# VF_OrdRes_PCB.net
KiCad netlist of a schematic drawn in EAGLE
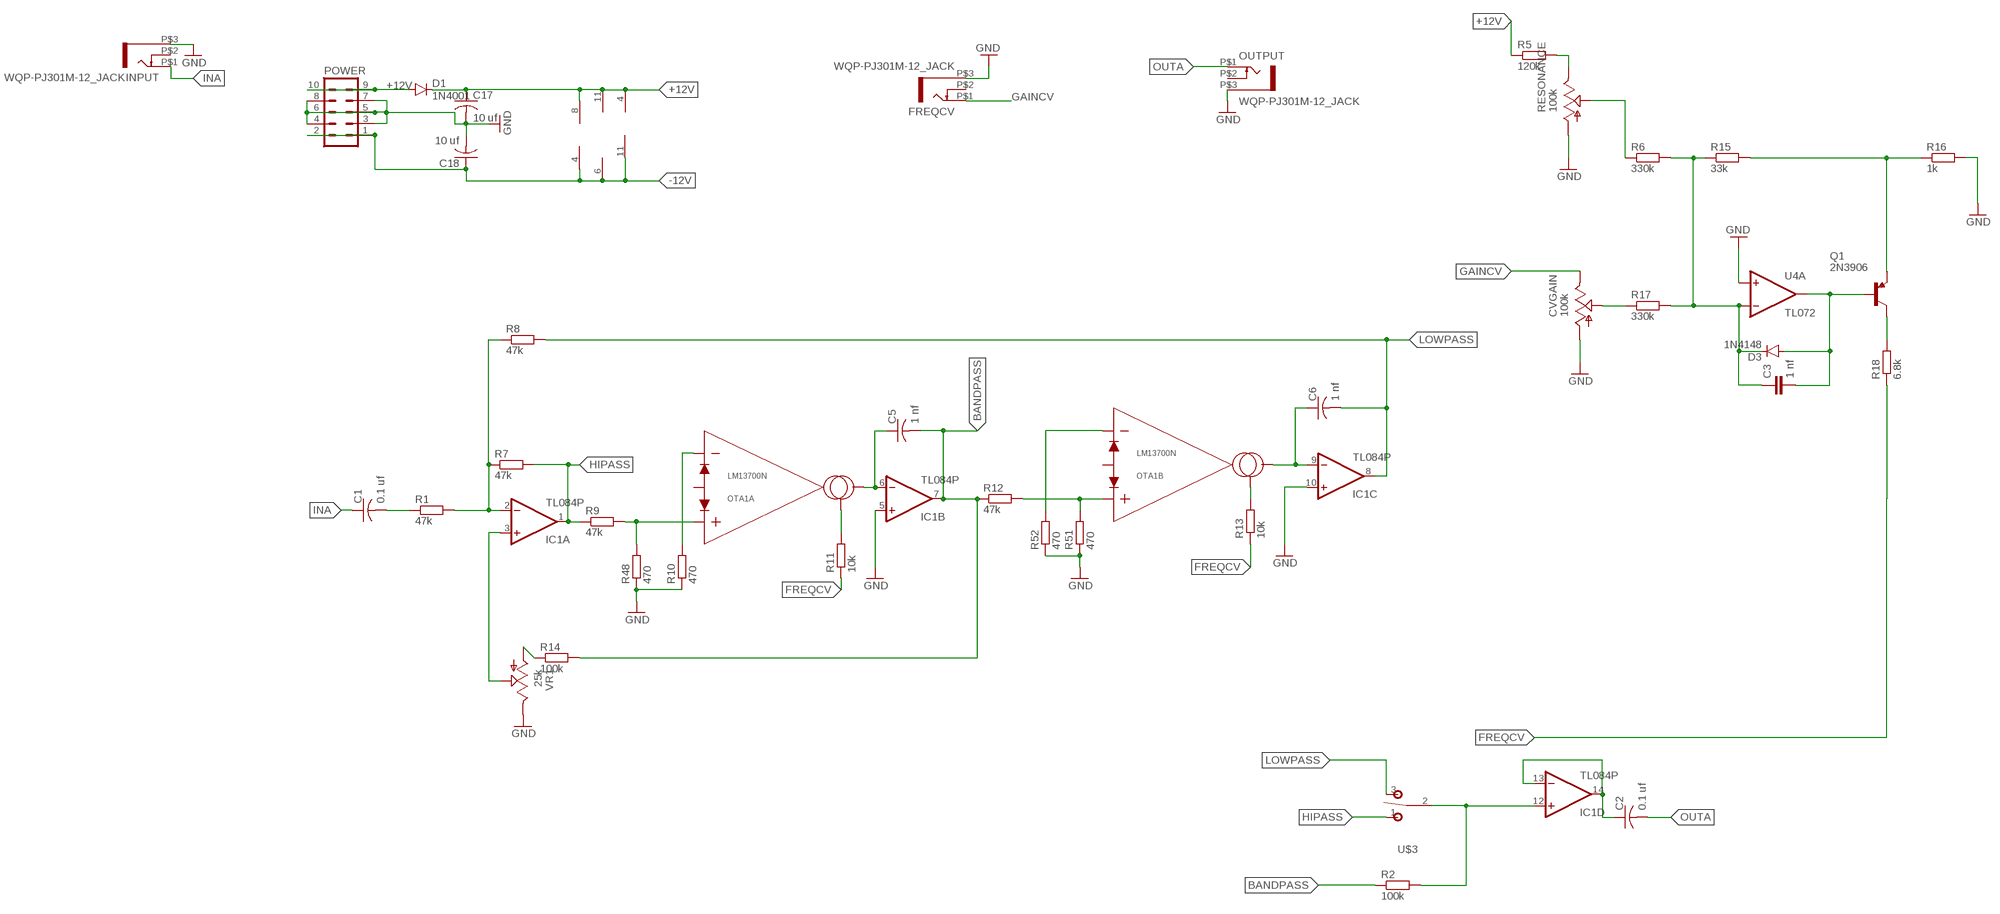
[diagram p0: schematic, sheet 1]

(export (version "E")
  (design (tool "Eeschema 10.0.6"))
  (components
    (comp (ref "C1")
      (value "0.1 uf")
      (footprint "eagle-import:C050-030X075")
      (libsource (lib "eagle-import") (part "C-US050-030X075"))
    )
    (comp (ref "C2")
      (value "0.1 uf")
      (footprint "eagle-import:C050-030X075")
      (libsource (lib "eagle-import") (part "C-US050-030X075"))
    )
    (comp (ref "C3")
      (value "1 nf")
      (footprint "eagle-import:C050-025X075")
      (libsource (lib "eagle-import") (part "C-EU050-025X075"))
    )
    (comp (ref "C5")
      (value "1 nf")
      (footprint "eagle-import:C050-030X075")
      (libsource (lib "eagle-import") (part "C-US050-030X075"))
    )
    (comp (ref "C6")
      (value "1 nf")
      (footprint "eagle-import:C050-030X075")
      (libsource (lib "eagle-import") (part "C-US050-030X075"))
    )
    (comp (ref "C17")
      (value "10 uf")
      (footprint "eagle-import:C050-030X075")
      (libsource (lib "eagle-import") (part "C-US050-030X075"))
    )
    (comp (ref "C18")
      (value "10 uf")
      (footprint "eagle-import:C050-030X075")
      (libsource (lib "eagle-import") (part "C-US050-030X075"))
    )
    (comp (ref "CVGAIN")
      (value "100k")
      (footprint "eagle-import:9MM_SNAP-IN_POT")
      (libsource (lib "eagle-import") (part "9MM_SNAP-IN_POT_"))
    )
    (comp (ref "D1")
      (value "1N4001")
      (footprint "eagle-import:DO41-10")
      (libsource (lib "eagle-import") (part "1N4004"))
    )
    (comp (ref "D3")
      (value "1N4148")
      (footprint "eagle-import:DO35-7")
      (libsource (lib "eagle-import") (part "1N4148DO35-7"))
    )
    (comp (ref "FREQCV")
      (value "WQP-PJ301M-12_JACK")
      (footprint "eagle-import:WQP-PJ301M-12_JACK")
      (libsource (lib "eagle-import") (part "WQP-PJ301M-12_JACK"))
    )
    (comp (ref "IC1")
      (value "TL084P")
      (footprint "eagle-import:DIL14")
      (libsource (lib "eagle-import") (part "TL084P"))
    )
    (comp (ref "INPUT")
      (value "WQP-PJ301M-12_JACK")
      (footprint "eagle-import:WQP-PJ301M-12_JACK")
      (libsource (lib "eagle-import") (part "WQP-PJ301M-12_JACK"))
    )
    (comp (ref "OTA1")
      (value "LM13700N")
      (footprint "eagle-import:DIP16")
      (libsource (lib "eagle-import") (part "LM13700N"))
    )
    (comp (ref "OUTPUT")
      (value "WQP-PJ301M-12_JACK")
      (footprint "eagle-import:WQP-PJ301M-12_JACK")
      (libsource (lib "eagle-import") (part "WQP-PJ301M-12_JACK"))
    )
    (comp (ref "POWER")
      (value "10_PIN_HEADER")
      (footprint "eagle-import:MA05-2")
      (libsource (lib "eagle-import") (part "10_PIN_HEADER"))
    )
    (comp (ref "Q1")
      (value "2N3906")
      (footprint "eagle-import:TO92")
      (libsource (lib "eagle-import") (part "2N3906"))
    )
    (comp (ref "R1")
      (value "47k")
      (footprint "eagle-import:7MM_RESISTOR")
      (libsource (lib "eagle-import") (part "RESISTOR7MM"))
    )
    (comp (ref "R2")
      (value "100k")
      (footprint "eagle-import:7MM_RESISTOR")
      (libsource (lib "eagle-import") (part "RESISTOR7MM"))
    )
    (comp (ref "R5")
      (value "120k")
      (footprint "eagle-import:7MM_RESISTOR")
      (libsource (lib "eagle-import") (part "RESISTOR7MM"))
    )
    (comp (ref "R6")
      (value "330k")
      (footprint "eagle-import:7MM_RESISTOR")
      (libsource (lib "eagle-import") (part "RESISTOR7MM"))
    )
    (comp (ref "R7")
      (value "47k")
      (footprint "eagle-import:7MM_RESISTOR")
      (libsource (lib "eagle-import") (part "RESISTOR7MM"))
    )
    (comp (ref "R8")
      (value "47k")
      (footprint "eagle-import:7MM_RESISTOR")
      (libsource (lib "eagle-import") (part "RESISTOR7MM"))
    )
    (comp (ref "R9")
      (value "47k")
      (footprint "eagle-import:7MM_RESISTOR")
      (libsource (lib "eagle-import") (part "RESISTOR7MM"))
    )
    (comp (ref "R10")
      (value "470")
      (footprint "eagle-import:7MM_RESISTOR")
      (libsource (lib "eagle-import") (part "RESISTOR7MM"))
    )
    (comp (ref "R11")
      (value "10k")
      (footprint "eagle-import:7MM_RESISTOR")
      (libsource (lib "eagle-import") (part "RESISTOR7MM"))
    )
    (comp (ref "R12")
      (value "47k")
      (footprint "eagle-import:7MM_RESISTOR")
      (libsource (lib "eagle-import") (part "RESISTOR7MM"))
    )
    (comp (ref "R13")
      (value "10k")
      (footprint "eagle-import:7MM_RESISTOR")
      (libsource (lib "eagle-import") (part "RESISTOR7MM"))
    )
    (comp (ref "R14")
      (value "100k")
      (footprint "eagle-import:7MM_RESISTOR")
      (libsource (lib "eagle-import") (part "RESISTOR7MM"))
    )
    (comp (ref "R15")
      (value "33k")
      (footprint "eagle-import:7MM_RESISTOR")
      (libsource (lib "eagle-import") (part "RESISTOR7MM"))
    )
    (comp (ref "R16")
      (value "1k")
      (footprint "eagle-import:7MM_RESISTOR")
      (libsource (lib "eagle-import") (part "RESISTOR7MM"))
    )
    (comp (ref "R17")
      (value "330k")
      (footprint "eagle-import:7MM_RESISTOR")
      (libsource (lib "eagle-import") (part "RESISTOR7MM"))
    )
    (comp (ref "R18")
      (value "6.8k")
      (footprint "eagle-import:7MM_RESISTOR")
      (libsource (lib "eagle-import") (part "RESISTOR7MM"))
    )
    (comp (ref "R48")
      (value "470")
      (footprint "eagle-import:7MM_RESISTOR")
      (libsource (lib "eagle-import") (part "RESISTOR7MM"))
    )
    (comp (ref "R51")
      (value "470")
      (footprint "eagle-import:7MM_RESISTOR")
      (libsource (lib "eagle-import") (part "RESISTOR7MM"))
    )
    (comp (ref "R52")
      (value "470")
      (footprint "eagle-import:7MM_RESISTOR")
      (libsource (lib "eagle-import") (part "RESISTOR7MM"))
    )
    (comp (ref "RESONANCE")
      (value "100k")
      (footprint "eagle-import:9MM_SNAP-IN_POT")
      (libsource (lib "eagle-import") (part "9MM_SNAP-IN_POT_"))
    )
    (comp (ref "U$3")
      (value "T-80-T-SPDT-ON-OFF-ON")
      (footprint "eagle-import:M9040P")
      (libsource (lib "eagle-import") (part "T-80-T-SPDT-ON-OFF-ON"))
    )
    (comp (ref "U4")
      (value "TL072")
      (footprint "eagle-import:DIL08-SML")
      (libsource (lib "eagle-import") (part "TL072"))
    )
    (comp (ref "VR1")
      (value "25k")
      (footprint "eagle-import:9MM_SNAP-IN_POT")
      (libsource (lib "eagle-import") (part "9MM_SNAP-IN_POT_"))
    )
  )
  (nets
    (net (code "1") (name "+12V") (class "Default")
      (node (ref "C17") (pin "1") (pinfunction "1_1") (pintype "passive"))
      (node (ref "D1") (pin "C") (pinfunction "C_C") (pintype "passive"))
      (node (ref "IC1") (pin "4") (pinfunction "V+_4") (pintype "power_in"))
      (node (ref "OTA1") (pin "11") (pinfunction "VCC_11") (pintype "power_in"))
      (node (ref "R5") (pin "1") (pinfunction "1_1") (pintype "passive"))
      (node (ref "U4") (pin "8") (pinfunction "V+_8") (pintype "power_in"))
    )
    (net (code "2") (name "-12V") (class "Default")
      (node (ref "C18") (pin "1") (pinfunction "1_1") (pintype "passive"))
      (node (ref "IC1") (pin "11") (pinfunction "V-_11") (pintype "power_in"))
      (node (ref "OTA1") (pin "6") (pinfunction "VEE_6") (pintype "power_in"))
      (node (ref "POWER") (pin "1") (pinfunction "1_1") (pintype "passive"))
      (node (ref "POWER") (pin "2") (pinfunction "2_2") (pintype "passive"))
      (node (ref "U4") (pin "4") (pinfunction "V-_4") (pintype "power_in"))
    )
    (net (code "3") (name "BANDPASS") (class "Default")
      (node (ref "C5") (pin "2") (pinfunction "2_2") (pintype "passive"))
      (node (ref "IC1") (pin "7") (pinfunction "OUT_7") (pintype "output"))
      (node (ref "R12") (pin "1") (pinfunction "1_1") (pintype "passive"))
      (node (ref "R14") (pin "2") (pinfunction "2_2") (pintype "passive"))
      (node (ref "R2") (pin "1") (pinfunction "1_1") (pintype "passive"))
    )
    (net (code "4") (name "FREQCV") (class "Default")
      (node (ref "R11") (pin "1") (pinfunction "1_1") (pintype "passive"))
      (node (ref "R13") (pin "1") (pinfunction "1_1") (pintype "passive"))
      (node (ref "R18") (pin "1") (pinfunction "1_1") (pintype "passive"))
    )
    (net (code "5") (name "GAINCV") (class "Default")
      (node (ref "CVGAIN") (pin "3") (pinfunction "E_3") (pintype "passive"))
      (node (ref "FREQCV") (pin "P$1") (pinfunction "2_P$1") (pintype "passive"))
    )
    (net (code "6") (name "GND") (class "Default")
      (node (ref "C17") (pin "2") (pinfunction "2_2") (pintype "passive"))
      (node (ref "C18") (pin "2") (pinfunction "2_2") (pintype "passive"))
      (node (ref "CVGAIN") (pin "1") (pinfunction "A_1") (pintype "passive"))
      (node (ref "FREQCV") (pin "P$3") (pinfunction "1_P$3") (pintype "passive"))
      (node (ref "IC1") (pin "10") (pinfunction "+IN_10") (pintype "input"))
      (node (ref "IC1") (pin "5") (pinfunction "+IN_5") (pintype "input"))
      (node (ref "INPUT") (pin "P$3") (pinfunction "1_P$3") (pintype "passive"))
      (node (ref "OUTPUT") (pin "P$3") (pinfunction "1_P$3") (pintype "passive"))
      (node (ref "POWER") (pin "3") (pinfunction "3_3") (pintype "passive"))
      (node (ref "POWER") (pin "4") (pinfunction "4_4") (pintype "passive"))
      (node (ref "POWER") (pin "5") (pinfunction "5_5") (pintype "passive"))
      (node (ref "POWER") (pin "6") (pinfunction "6_6") (pintype "passive"))
      (node (ref "POWER") (pin "7") (pinfunction "7_7") (pintype "passive"))
      (node (ref "POWER") (pin "8") (pinfunction "8_8") (pintype "passive"))
      (node (ref "R10") (pin "1") (pinfunction "1_1") (pintype "passive"))
      (node (ref "R16") (pin "2") (pinfunction "2_2") (pintype "passive"))
      (node (ref "R48") (pin "1") (pinfunction "1_1") (pintype "passive"))
      (node (ref "R51") (pin "1") (pinfunction "1_1") (pintype "passive"))
      (node (ref "R52") (pin "1") (pinfunction "1_1") (pintype "passive"))
      (node (ref "RESONANCE") (pin "1") (pinfunction "A_1") (pintype "passive"))
      (node (ref "U4") (pin "3") (pinfunction "+IN_3") (pintype "input"))
      (node (ref "VR1") (pin "3") (pinfunction "E_3") (pintype "passive"))
    )
    (net (code "7") (name "HIPASS") (class "Default")
      (node (ref "IC1") (pin "1") (pinfunction "OUT_1") (pintype "output"))
      (node (ref "R7") (pin "2") (pinfunction "2_2") (pintype "passive"))
      (node (ref "R9") (pin "1") (pinfunction "1_1") (pintype "passive"))
      (node (ref "U$3") (pin "1") (pinfunction "O_1") (pintype "passive"))
    )
    (net (code "8") (name "INA") (class "Default")
      (node (ref "C1") (pin "1") (pinfunction "1_1") (pintype "passive"))
      (node (ref "INPUT") (pin "P$1") (pinfunction "2_P$1") (pintype "passive"))
    )
    (net (code "9") (name "LOWPASS") (class "Default")
      (node (ref "C6") (pin "2") (pinfunction "2_2") (pintype "passive"))
      (node (ref "IC1") (pin "8") (pinfunction "OUT_8") (pintype "output"))
      (node (ref "R8") (pin "2") (pinfunction "2_2") (pintype "passive"))
      (node (ref "U$3") (pin "3") (pinfunction "S_3") (pintype "passive"))
    )
    (net (code "10") (name "Net-(C1-Pad2)") (class "Default")
      (node (ref "C1") (pin "2") (pinfunction "2_2") (pintype "passive"))
      (node (ref "R1") (pin "1") (pinfunction "1_1") (pintype "passive"))
    )
    (net (code "11") (name "Net-(CVGAIN-S)") (class "Default")
      (node (ref "CVGAIN") (pin "2") (pinfunction "S_2") (pintype "passive"))
      (node (ref "R17") (pin "1") (pinfunction "1_1") (pintype "passive"))
    )
    (net (code "12") (name "Net-(D1-PadA)") (class "Default")
      (node (ref "D1") (pin "A") (pinfunction "A_A") (pintype "passive"))
      (node (ref "POWER") (pin "10") (pinfunction "10_10") (pintype "passive"))
      (node (ref "POWER") (pin "9") (pinfunction "9_9") (pintype "passive"))
    )
    (net (code "13") (name "Net-(IC1A-+IN)") (class "Default")
      (node (ref "IC1") (pin "3") (pinfunction "+IN_3") (pintype "input"))
      (node (ref "VR1") (pin "2") (pinfunction "S_2") (pintype "passive"))
    )
    (net (code "14") (name "Net-(IC1A--IN)") (class "Default")
      (node (ref "IC1") (pin "2") (pinfunction "-IN_2") (pintype "input"))
      (node (ref "R1") (pin "2") (pinfunction "2_2") (pintype "passive"))
      (node (ref "R7") (pin "1") (pinfunction "1_1") (pintype "passive"))
      (node (ref "R8") (pin "1") (pinfunction "1_1") (pintype "passive"))
    )
    (net (code "15") (name "Net-(IC1B--IN)") (class "Default")
      (node (ref "C5") (pin "1") (pinfunction "1_1") (pintype "passive"))
      (node (ref "IC1") (pin "6") (pinfunction "-IN_6") (pintype "input"))
      (node (ref "OTA1") (pin "5") (pinfunction "IOUT_5") (pintype "output"))
    )
    (net (code "16") (name "Net-(IC1C--IN)") (class "Default")
      (node (ref "C6") (pin "1") (pinfunction "1_1") (pintype "passive"))
      (node (ref "IC1") (pin "9") (pinfunction "-IN_9") (pintype "input"))
      (node (ref "OTA1") (pin "12") (pinfunction "IOUT_12") (pintype "output"))
    )
    (net (code "17") (name "Net-(IC1D-+IN)") (class "Default")
      (node (ref "IC1") (pin "12") (pinfunction "+IN_12") (pintype "input"))
      (node (ref "R2") (pin "2") (pinfunction "2_2") (pintype "passive"))
      (node (ref "U$3") (pin "2") (pinfunction "P_2") (pintype "passive"))
    )
    (net (code "18") (name "Net-(IC1D--IN)") (class "Default")
      (node (ref "C2") (pin "1") (pinfunction "1_1") (pintype "passive"))
      (node (ref "IC1") (pin "13") (pinfunction "-IN_13") (pintype "input"))
      (node (ref "IC1") (pin "14") (pinfunction "OUT_14") (pintype "output"))
    )
    (net (code "19") (name "Net-(OTA1A-IABC)") (class "Default")
      (node (ref "OTA1") (pin "1") (pinfunction "IABC_1") (pintype "input"))
      (node (ref "R11") (pin "2") (pinfunction "2_2") (pintype "passive"))
    )
    (net (code "20") (name "Net-(OTA1A-IN+)") (class "Default")
      (node (ref "OTA1") (pin "3") (pinfunction "IN+_3") (pintype "input"))
      (node (ref "R48") (pin "2") (pinfunction "2_2") (pintype "passive"))
      (node (ref "R9") (pin "2") (pinfunction "2_2") (pintype "passive"))
    )
    (net (code "21") (name "Net-(OTA1A-IN-)") (class "Default")
      (node (ref "OTA1") (pin "4") (pinfunction "IN-_4") (pintype "input"))
      (node (ref "R10") (pin "2") (pinfunction "2_2") (pintype "passive"))
    )
    (net (code "22") (name "Net-(OTA1B-IABC)") (class "Default")
      (node (ref "OTA1") (pin "16") (pinfunction "IABC_16") (pintype "input"))
      (node (ref "R13") (pin "2") (pinfunction "2_2") (pintype "passive"))
    )
    (net (code "23") (name "Net-(OTA1B-IN+)") (class "Default")
      (node (ref "OTA1") (pin "14") (pinfunction "IN+_14") (pintype "input"))
      (node (ref "R12") (pin "2") (pinfunction "2_2") (pintype "passive"))
      (node (ref "R51") (pin "2") (pinfunction "2_2") (pintype "passive"))
    )
    (net (code "24") (name "Net-(OTA1B-IN-)") (class "Default")
      (node (ref "OTA1") (pin "13") (pinfunction "IN-_13") (pintype "input"))
      (node (ref "R52") (pin "2") (pinfunction "2_2") (pintype "passive"))
    )
    (net (code "25") (name "Net-(Q1-B)") (class "Default")
      (node (ref "C3") (pin "2") (pinfunction "2_2") (pintype "passive"))
      (node (ref "D3") (pin "A") (pinfunction "A_A") (pintype "passive"))
      (node (ref "Q1") (pin "2") (pinfunction "B_2") (pintype "passive"))
      (node (ref "U4") (pin "1") (pinfunction "OUT_1") (pintype "output"))
    )
    (net (code "26") (name "Net-(Q1-C)") (class "Default")
      (node (ref "Q1") (pin "1") (pinfunction "C_1") (pintype "passive"))
      (node (ref "R18") (pin "2") (pinfunction "2_2") (pintype "passive"))
    )
    (net (code "27") (name "Net-(Q1-E)") (class "Default")
      (node (ref "Q1") (pin "3") (pinfunction "E_3") (pintype "passive"))
      (node (ref "R15") (pin "2") (pinfunction "2_2") (pintype "passive"))
      (node (ref "R16") (pin "1") (pinfunction "1_1") (pintype "passive"))
    )
    (net (code "28") (name "Net-(RESONANCE-E)") (class "Default")
      (node (ref "R5") (pin "2") (pinfunction "2_2") (pintype "passive"))
      (node (ref "RESONANCE") (pin "3") (pinfunction "E_3") (pintype "passive"))
    )
    (net (code "29") (name "Net-(RESONANCE-S)") (class "Default")
      (node (ref "R6") (pin "1") (pinfunction "1_1") (pintype "passive"))
      (node (ref "RESONANCE") (pin "2") (pinfunction "S_2") (pintype "passive"))
    )
    (net (code "30") (name "Net-(U4A--IN)") (class "Default")
      (node (ref "C3") (pin "1") (pinfunction "1_1") (pintype "passive"))
      (node (ref "D3") (pin "C") (pinfunction "C_C") (pintype "passive"))
      (node (ref "R15") (pin "1") (pinfunction "1_1") (pintype "passive"))
      (node (ref "R17") (pin "2") (pinfunction "2_2") (pintype "passive"))
      (node (ref "R6") (pin "2") (pinfunction "2_2") (pintype "passive"))
      (node (ref "U4") (pin "2") (pinfunction "-IN_2") (pintype "input"))
    )
    (net (code "31") (name "Net-(VR1-A)") (class "Default")
      (node (ref "R14") (pin "1") (pinfunction "1_1") (pintype "passive"))
      (node (ref "VR1") (pin "1") (pinfunction "A_1") (pintype "passive"))
    )
    (net (code "32") (name "OUTA") (class "Default")
      (node (ref "C2") (pin "2") (pinfunction "2_2") (pintype "passive"))
      (node (ref "OUTPUT") (pin "P$1") (pinfunction "2_P$1") (pintype "passive"))
    )
    (net (code "33") (name "unconnected-(FREQCV-3-PadP$2)") (class "Default")
      (node (ref "FREQCV") (pin "P$2") (pinfunction "3_P$2") (pintype "passive"))
    )
    (net (code "34") (name "unconnected-(INPUT-3-PadP$2)") (class "Default")
      (node (ref "INPUT") (pin "P$2") (pinfunction "3_P$2") (pintype "passive"))
    )
    (net (code "35") (name "unconnected-(OTA1A-BIAS-Pad2)") (class "Default")
      (node (ref "OTA1") (pin "2") (pinfunction "BIAS_2") (pintype "input"))
    )
    (net (code "36") (name "unconnected-(OTA1B-BIAS-Pad15)") (class "Default")
      (node (ref "OTA1") (pin "15") (pinfunction "BIAS_15") (pintype "input"))
    )
    (net (code "37") (name "unconnected-(OUTPUT-3-PadP$2)") (class "Default")
      (node (ref "OUTPUT") (pin "P$2") (pinfunction "3_P$2") (pintype "passive"))
    )
  )
)
